# TeamB_PDS.net
KiCad netlist of a schematic drawn in EAGLE
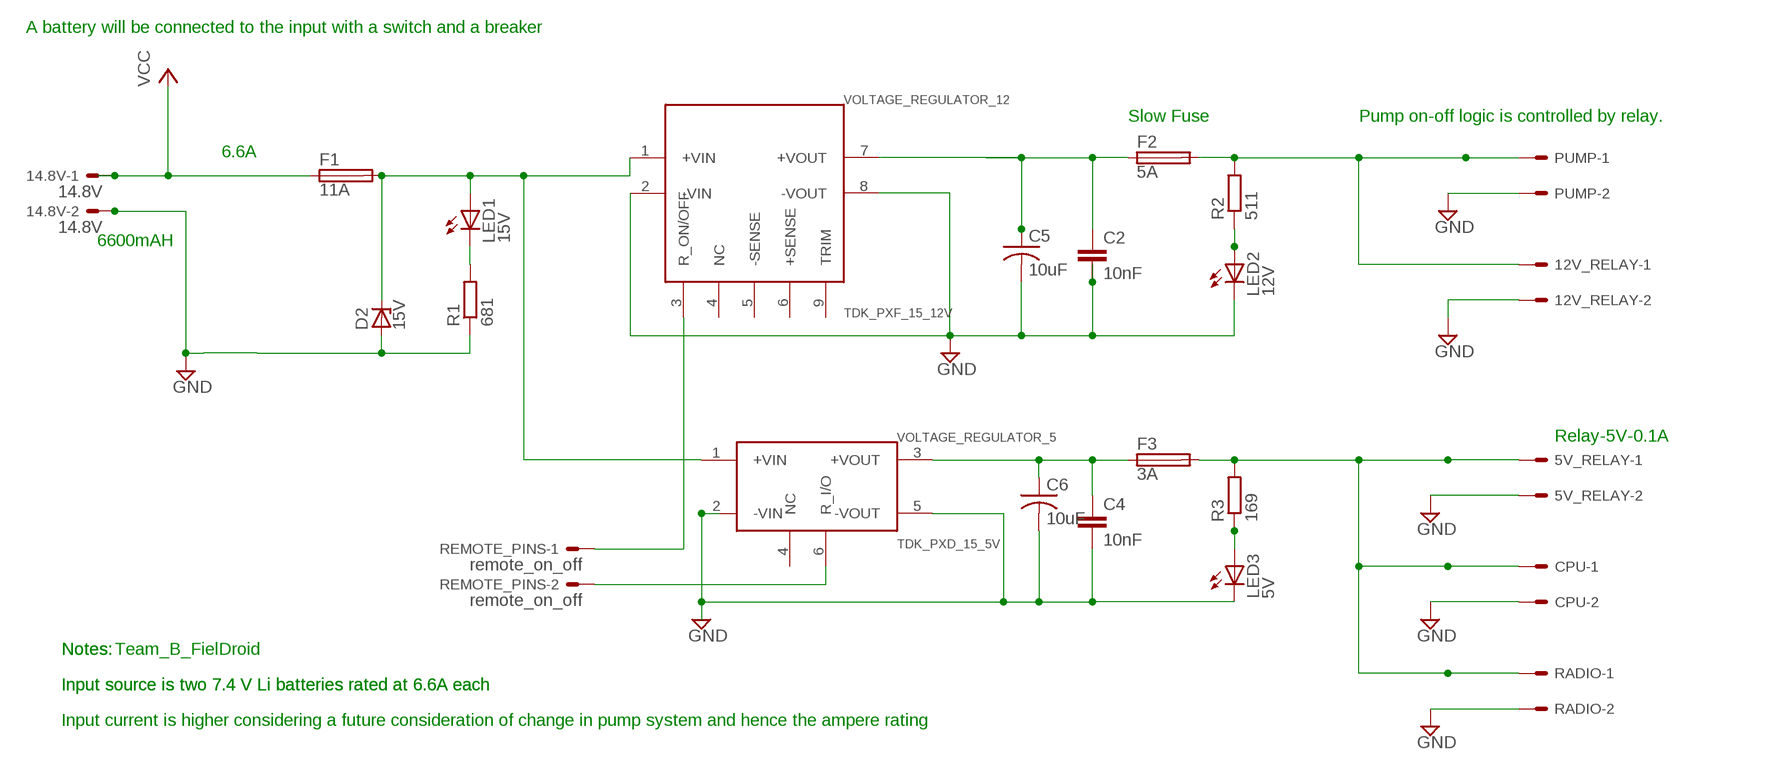
[diagram p0: schematic, sheet 1]

(export (version "E")
  (design (tool "Eeschema 10.0.6"))
  (components
    (comp (ref "5V_RELAY")
      (value "5566-2")
      (footprint "eagle-import:5566-2")
      (libsource (lib "eagle-import") (part "5566-2"))
    )
    (comp (ref "12V_RELAY")
      (value "5566-2")
      (footprint "eagle-import:5566-2")
      (libsource (lib "eagle-import") (part "5566-2"))
    )
    (comp (ref "14.8V")
      (value "14.8V")
      (footprint "eagle-import:5566-2")
      (libsource (lib "eagle-import") (part "5566-2"))
    )
    (comp (ref "C2")
      (value "10nF")
      (footprint "eagle-import:C2.5-4")
      (libsource (lib "eagle-import") (part "C2.5/4"))
    )
    (comp (ref "C4")
      (value "10nF")
      (footprint "eagle-import:C2.5-4")
      (libsource (lib "eagle-import") (part "C2.5/4"))
    )
    (comp (ref "C5")
      (value "10uF")
      (footprint "eagle-import:C050-024X044")
      (libsource (lib "eagle-import") (part "C-US050-024X044"))
    )
    (comp (ref "C6")
      (value "10uF")
      (footprint "eagle-import:C050-024X044")
      (libsource (lib "eagle-import") (part "C-US050-024X044"))
    )
    (comp (ref "CPU")
      (value "5566-2")
      (footprint "eagle-import:5566-2")
      (libsource (lib "eagle-import") (part "5566-2"))
    )
    (comp (ref "D2")
      (value "15V")
      (footprint "eagle-import:ZDIO-5")
      (libsource (lib "eagle-import") (part "ZENER-DIODEZD-5"))
    )
    (comp (ref "F1")
      (value "11A")
      (footprint "eagle-import:FUSE_HOLDER_5X20MM")
      (libsource (lib "eagle-import") (part "FUSEBLANK_5X20MM"))
    )
    (comp (ref "F2")
      (value "5A")
      (footprint "eagle-import:FUSE_HOLDER_5X20MM")
      (libsource (lib "eagle-import") (part "FUSEBLANK_5X20MM"))
    )
    (comp (ref "F3")
      (value "3A")
      (footprint "eagle-import:FUSE_HOLDER_5X20MM")
      (libsource (lib "eagle-import") (part "FUSEBLANK_5X20MM"))
    )
    (comp (ref "LED1")
      (value "15V")
      (footprint "eagle-import:LED5MM")
      (libsource (lib "eagle-import") (part "LED5MM"))
    )
    (comp (ref "LED2")
      (value "12V")
      (footprint "eagle-import:LED5MM")
      (libsource (lib "eagle-import") (part "LED5MM"))
    )
    (comp (ref "LED3")
      (value "5V")
      (footprint "eagle-import:LED5MM")
      (libsource (lib "eagle-import") (part "LED5MM"))
    )
    (comp (ref "PUMP")
      (value "5566-2")
      (footprint "eagle-import:5566-2")
      (libsource (lib "eagle-import") (part "5566-2"))
    )
    (comp (ref "R1")
      (value "681")
      (footprint "eagle-import:0204_7")
      (libsource (lib "eagle-import") (part "R-EU_0204/7"))
    )
    (comp (ref "R2")
      (value "511")
      (footprint "eagle-import:0204_7")
      (libsource (lib "eagle-import") (part "R-EU_0204/7"))
    )
    (comp (ref "R3")
      (value "169")
      (footprint "eagle-import:0204_7")
      (libsource (lib "eagle-import") (part "R-EU_0204/7"))
    )
    (comp (ref "RADIO")
      (value "5566-2")
      (footprint "eagle-import:5566-2")
      (libsource (lib "eagle-import") (part "5566-2"))
    )
    (comp (ref "REMOTE_PINS")
      (value "remote_on_off")
      (footprint "eagle-import:5566-2")
      (libsource (lib "eagle-import") (part "5566-2"))
    )
    (comp (ref "VOLTAGE_REGULATOR_5")
      (value "TDK_PXD_15_5V")
      (footprint "eagle-import:TDK-PXD_15-5V")
      (libsource (lib "eagle-import") (part "TDK_PXD_15_5V"))
    )
    (comp (ref "VOLTAGE_REGULATOR_12")
      (value "TDK_PXF_15_12V")
      (footprint "eagle-import:TDK_PXF_15_12V")
      (libsource (lib "eagle-import") (part "TDK_PXF_15_12V"))
    )
  )
  (nets
    (net (code "1") (name "GND") (class "Default")
      (node (ref "12V_RELAY") (pin "2") (pinfunction "S_2") (pintype "passive"))
      (node (ref "14.8V") (pin "2") (pinfunction "S_2") (pintype "passive"))
      (node (ref "5V_RELAY") (pin "2") (pinfunction "S_2") (pintype "passive"))
      (node (ref "C2") (pin "2") (pinfunction "2_2") (pintype "passive"))
      (node (ref "C4") (pin "2") (pinfunction "2_2") (pintype "passive"))
      (node (ref "C5") (pin "2") (pinfunction "2_2") (pintype "passive"))
      (node (ref "C6") (pin "2") (pinfunction "2_2") (pintype "passive"))
      (node (ref "CPU") (pin "2") (pinfunction "S_2") (pintype "passive"))
      (node (ref "D2") (pin "A") (pinfunction "A_A") (pintype "passive"))
      (node (ref "LED2") (pin "K") (pinfunction "C_K") (pintype "passive"))
      (node (ref "LED3") (pin "K") (pinfunction "C_K") (pintype "passive"))
      (node (ref "PUMP") (pin "2") (pinfunction "S_2") (pintype "passive"))
      (node (ref "R1") (pin "1") (pinfunction "1_1") (pintype "passive"))
      (node (ref "RADIO") (pin "2") (pinfunction "S_2") (pintype "passive"))
      (node (ref "VOLTAGE_REGULATOR_12") (pin "2") (pinfunction "-VIN_2") (pintype "bidirectional"))
      (node (ref "VOLTAGE_REGULATOR_12") (pin "8") (pinfunction "-VOUT_8") (pintype "bidirectional"))
      (node (ref "VOLTAGE_REGULATOR_5") (pin "2") (pinfunction "-VIN_2") (pintype "bidirectional"))
      (node (ref "VOLTAGE_REGULATOR_5") (pin "5") (pinfunction "-VOUT_5") (pintype "bidirectional"))
    )
    (net (code "2") (name "Net-(5V_RELAYA-S)") (class "Default")
      (node (ref "5V_RELAY") (pin "1") (pinfunction "S_1") (pintype "passive"))
      (node (ref "CPU") (pin "1") (pinfunction "S_1") (pintype "passive"))
      (node (ref "F3") (pin "2") (pinfunction "2_2") (pintype "passive"))
      (node (ref "R3") (pin "2") (pinfunction "2_2") (pintype "passive"))
      (node (ref "RADIO") (pin "1") (pinfunction "S_1") (pintype "passive"))
    )
    (net (code "3") (name "Net-(12V_RELAYA-S)") (class "Default")
      (node (ref "12V_RELAY") (pin "1") (pinfunction "S_1") (pintype "passive"))
      (node (ref "F2") (pin "2") (pinfunction "2_2") (pintype "passive"))
      (node (ref "PUMP") (pin "1") (pinfunction "S_1") (pintype "passive"))
      (node (ref "R2") (pin "2") (pinfunction "2_2") (pintype "passive"))
    )
    (net (code "4") (name "Net-(LED1-C)") (class "Default")
      (node (ref "LED1") (pin "K") (pinfunction "C_K") (pintype "passive"))
      (node (ref "R1") (pin "2") (pinfunction "2_2") (pintype "passive"))
    )
    (net (code "5") (name "Net-(LED2-PadA)") (class "Default")
      (node (ref "LED2") (pin "A") (pinfunction "A_A") (pintype "passive"))
      (node (ref "R2") (pin "1") (pinfunction "1_1") (pintype "passive"))
    )
    (net (code "6") (name "Net-(LED3-PadA)") (class "Default")
      (node (ref "LED3") (pin "A") (pinfunction "A_A") (pintype "passive"))
      (node (ref "R3") (pin "1") (pinfunction "1_1") (pintype "passive"))
    )
    (net (code "7") (name "Net-(REMOTE_PINSA-S)") (class "Default")
      (node (ref "REMOTE_PINS") (pin "1") (pinfunction "S_1") (pintype "passive"))
      (node (ref "VOLTAGE_REGULATOR_12") (pin "3") (pinfunction "R_ON/OFF_3") (pintype "bidirectional"))
    )
    (net (code "8") (name "Net-(REMOTE_PINSB-S)") (class "Default")
      (node (ref "REMOTE_PINS") (pin "2") (pinfunction "S_2") (pintype "passive"))
      (node (ref "VOLTAGE_REGULATOR_5") (pin "6") (pinfunction "R_I/O_6") (pintype "bidirectional"))
    )
    (net (code "9") (name "Net-(VOLTAGE_REGULATOR_5-+VOUT)") (class "Default")
      (node (ref "C4") (pin "1") (pinfunction "1_1") (pintype "passive"))
      (node (ref "C6") (pin "1") (pinfunction "1_1") (pintype "passive"))
      (node (ref "F3") (pin "1") (pinfunction "1_1") (pintype "passive"))
      (node (ref "VOLTAGE_REGULATOR_5") (pin "3") (pinfunction "+VOUT_3") (pintype "bidirectional"))
    )
    (net (code "10") (name "Net-(VOLTAGE_REGULATOR_12-+VIN)") (class "Default")
      (node (ref "D2") (pin "C") (pinfunction "C_C") (pintype "passive"))
      (node (ref "F1") (pin "2") (pinfunction "2_2") (pintype "passive"))
      (node (ref "LED1") (pin "A") (pinfunction "A_A") (pintype "passive"))
      (node (ref "VOLTAGE_REGULATOR_12") (pin "1") (pinfunction "+VIN_1") (pintype "bidirectional"))
      (node (ref "VOLTAGE_REGULATOR_5") (pin "1") (pinfunction "+VIN_1") (pintype "bidirectional"))
    )
    (net (code "11") (name "Net-(VOLTAGE_REGULATOR_12-+VOUT)") (class "Default")
      (node (ref "C2") (pin "1") (pinfunction "1_1") (pintype "passive"))
      (node (ref "C5") (pin "1") (pinfunction "1_1") (pintype "passive"))
      (node (ref "F2") (pin "1") (pinfunction "1_1") (pintype "passive"))
      (node (ref "VOLTAGE_REGULATOR_12") (pin "7") (pinfunction "+VOUT_7") (pintype "bidirectional"))
    )
    (net (code "12") (name "VCC") (class "Default")
      (node (ref "14.8V") (pin "1") (pinfunction "S_1") (pintype "passive"))
      (node (ref "F1") (pin "1") (pinfunction "1_1") (pintype "passive"))
    )
    (net (code "13") (name "unconnected-(VOLTAGE_REGULATOR_5-NC-Pad4)") (class "Default")
      (node (ref "VOLTAGE_REGULATOR_5") (pin "4") (pinfunction "NC_4") (pintype "no_connect"))
    )
    (net (code "14") (name "unconnected-(VOLTAGE_REGULATOR_12-+SENSE-Pad6)") (class "Default")
      (node (ref "VOLTAGE_REGULATOR_12") (pin "6") (pinfunction "+SENSE_6") (pintype "bidirectional"))
    )
    (net (code "15") (name "unconnected-(VOLTAGE_REGULATOR_12--SENSE-Pad5)") (class "Default")
      (node (ref "VOLTAGE_REGULATOR_12") (pin "5") (pinfunction "-SENSE_5") (pintype "bidirectional"))
    )
    (net (code "16") (name "unconnected-(VOLTAGE_REGULATOR_12-NC-Pad4)") (class "Default")
      (node (ref "VOLTAGE_REGULATOR_12") (pin "4") (pinfunction "NC_4") (pintype "no_connect"))
    )
    (net (code "17") (name "unconnected-(VOLTAGE_REGULATOR_12-TRIM-Pad9)") (class "Default")
      (node (ref "VOLTAGE_REGULATOR_12") (pin "9") (pinfunction "TRIM_9") (pintype "bidirectional"))
    )
  )
)
